# CPU.net
KiCad netlist of a schematic drawn in Altium Designer
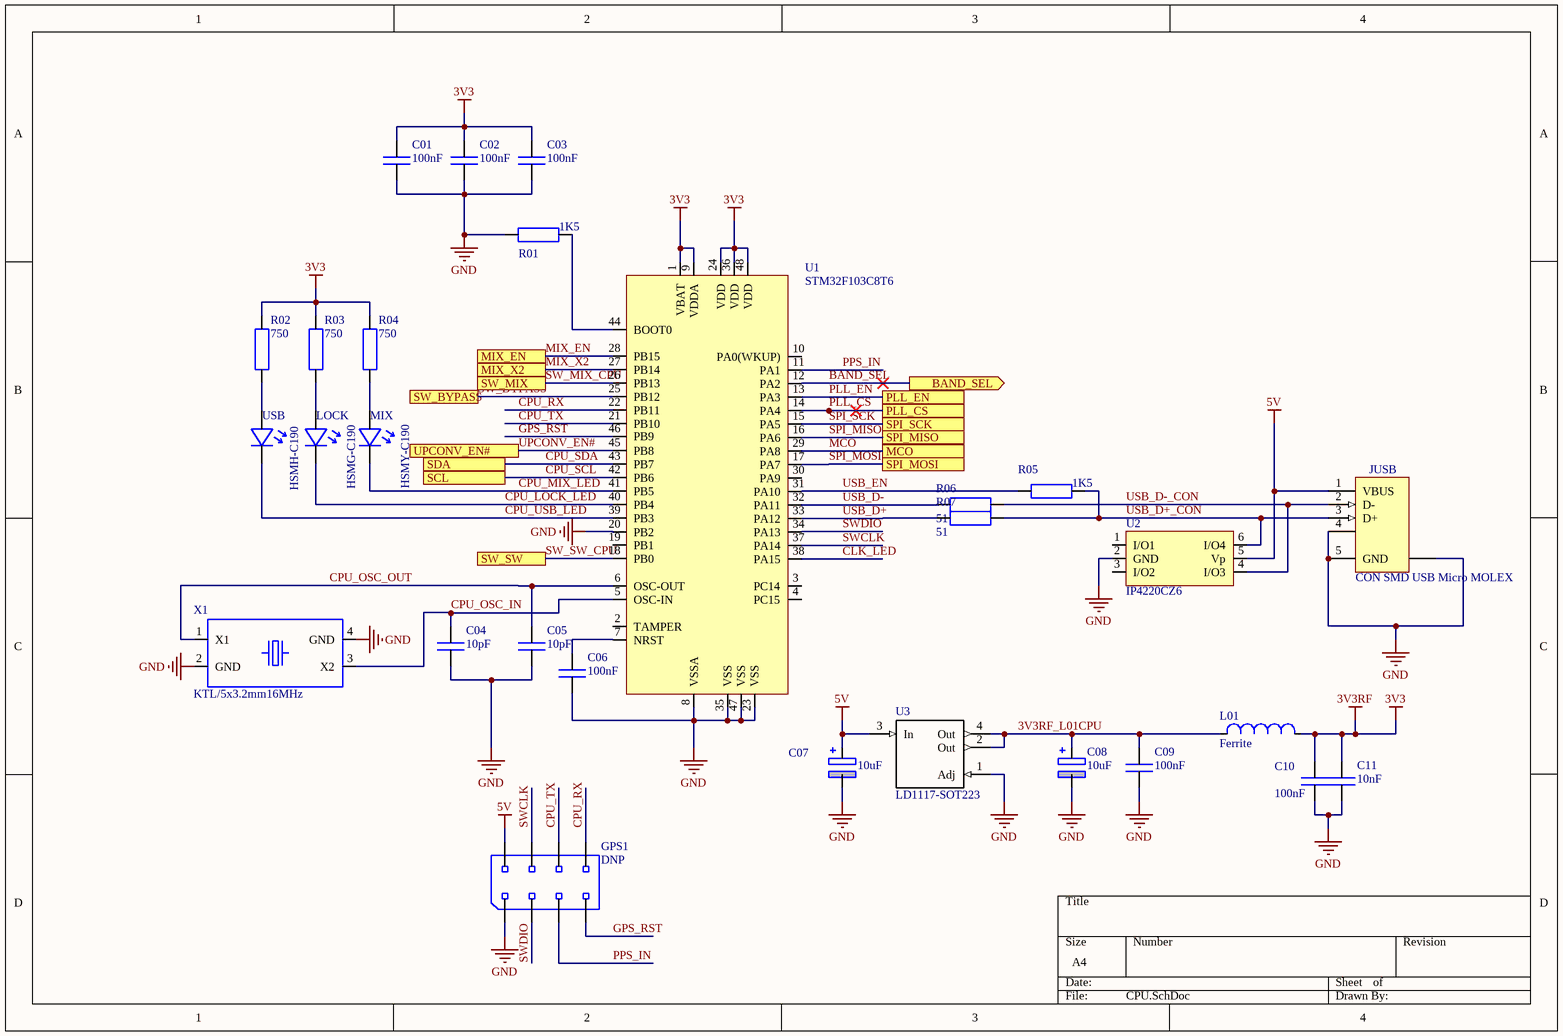
[diagram p0: CPU.SchDoc]

(export (version "E")
  (design (tool "Eeschema 10.0.6"))
  (components
    (comp (ref "C01")
      (value "100nF")
      (footprint "smd C0603_0.80")
      (description "smd capaciteit, verp.0603, 100nF")
      (fields (field (name "PART NUMBER") "CSMD603/100nF"))
      (libsource (lib "CDE_Library") (part "CSMD603/100nF"))
    )
    (comp (ref "C02")
      (value "100nF")
      (footprint "smd C0603_0.80")
      (description "smd capaciteit, verp.0603, 100nF")
      (fields (field (name "PART NUMBER") "CSMD603/100nF"))
      (libsource (lib "CDE_Library") (part "CSMD603/100nF"))
    )
    (comp (ref "C03")
      (value "100nF")
      (footprint "smd C0603_0.80")
      (description "smd capaciteit, verp.0603, 100nF")
      (fields (field (name "PART NUMBER") "CSMD603/100nF"))
      (libsource (lib "CDE_Library") (part "CSMD603/100nF"))
    )
    (comp (ref "C04")
      (value "10pF")
      (footprint "smd C0603_0.80")
      (description "smd capaciteit, verp.0603, 10pF")
      (fields (field (name "PART NUMBER") "CSMD603/10pF"))
      (libsource (lib "CDE_Library") (part "CSMD603/10pF"))
    )
    (comp (ref "C05")
      (value "10pF")
      (footprint "smd C0603_0.80")
      (description "smd capaciteit, verp.0603, 10pF")
      (fields (field (name "PART NUMBER") "CSMD603/10pF"))
      (libsource (lib "CDE_Library") (part "CSMD603/10pF"))
    )
    (comp (ref "C06")
      (value "100nF")
      (footprint "smd C0603_0.80")
      (description "smd capaciteit, verp.0603, 100nF")
      (fields (field (name "PART NUMBER") "CSMD603/100nF"))
      (libsource (lib "CDE_Library") (part "CSMD603/100nF"))
    )
    (comp (ref "C07")
      (value "10uF")
      (footprint "smd C1206 polar")
      (description "smd capaciteit, tantalium, verp.1206, 10uF/10V")
      (fields (field (name "PART NUMBER") "CSMD1206/10uF/10V"))
      (libsource (lib "CDE_Library") (part "CSMD1206/10uF/10V"))
    )
    (comp (ref "C08")
      (value "10uF")
      (footprint "smd C1206 polar")
      (description "smd capaciteit, tantalium, verp.1206, 10uF/10V")
      (fields (field (name "PART NUMBER") "CSMD1206/10uF/10V"))
      (libsource (lib "CDE_Library") (part "CSMD1206/10uF/10V"))
    )
    (comp (ref "C09")
      (value "100nF")
      (footprint "smd C0603_0.80")
      (description "smd capaciteit, verp.0603, 100nF")
      (fields (field (name "PART NUMBER") "CSMD603/100nF"))
      (libsource (lib "CDE_Library") (part "CSMD603/100nF"))
    )
    (comp (ref "C10")
      (value "100nF")
      (footprint "smd C0603_0.80")
      (description "smd capaciteit, verp.0603, 100nF")
      (fields (field (name "PART NUMBER") "CSMD603/100nF"))
      (libsource (lib "CDE_Library") (part "CSMD603/100nF"))
    )
    (comp (ref "C11")
      (value "10nF")
      (footprint "smd C0603_0.80")
      (description "smd capaciteit, verp.0603, 10nF")
      (fields (field (name "PART NUMBER") "CSMD603/10nF"))
      (libsource (lib "CDE_Library") (part "CSMD603/10nF"))
    )
    (comp (ref "GPS1")
      (value "DNP")
      (footprint "hdr 2x4")
      (description "pcb header recht 2x4  pitch 100mil")
      (fields (field (name "PART NUMBER") "CON HDR 2x4"))
      (libsource (lib "CDE_Library") (part "CON HDR 2x4"))
    )
    (comp (ref "JUSB")
      (value "CON SMD USB Micro MOLEX")
      (footprint "SMD USB MOLEX")
      (description "MOLEX - 47589-0001 - MICRO USB TYPE AB")
      (libsource (lib "CDE_Library") (part "CON SMD USB Micro MOLEX"))
    )
    (comp (ref "L01")
      (value "Ferrite")
      (footprint "smd C0805")
      (description "Ferrite bead, 0805 package")
      (libsource (lib "CDE_Library") (part "Ferrite 0805"))
    )
    (comp (ref "LOCK")
      (value "HSMG-C190")
      (footprint "led HSMH-C190 (Avago Technologies)")
      (description "led smd groen, Avago Techn., HSMG-C190")
      (libsource (lib "CDE_Library") (part "HSMG-C190"))
    )
    (comp (ref "MIX")
      (value "HSMY-C190")
      (footprint "led HSMH-C190 (Avago Technologies)")
      (description "led smd geel, Avago Techn., HSMY-C190")
      (libsource (lib "CDE_Library") (part "HSMY-C190"))
    )
    (comp (ref "R01")
      (value "1K5")
      (footprint "smd C0603_0.45")
      (description "weerstand SMD603, 1K5")
      (libsource (lib "CDE_Library") (part "1K5/603"))
    )
    (comp (ref "R02")
      (value "750")
      (footprint "smd C0603_0.45")
      (description "weerstand SMD603, 750R")
      (libsource (lib "CDE_Library") (part "750R/603"))
    )
    (comp (ref "R03")
      (value "750")
      (footprint "smd C0603_0.45")
      (description "weerstand SMD603, 750R")
      (libsource (lib "CDE_Library") (part "750R/603"))
    )
    (comp (ref "R04")
      (value "750")
      (footprint "smd C0603_0.45")
      (description "weerstand SMD603, 750R")
      (libsource (lib "CDE_Library") (part "750R/603"))
    )
    (comp (ref "R05")
      (value "1K5")
      (footprint "smd C0603_0.45")
      (description "weerstand SMD603, 1K5")
      (libsource (lib "CDE_Library") (part "1K5/603"))
    )
    (comp (ref "R06")
      (value "51")
      (footprint "smd C0603_0.45")
      (description "weerstand SMD603, 51R")
      (libsource (lib "CDE_Library") (part "51R/603"))
    )
    (comp (ref "R07")
      (value "51")
      (footprint "smd C0603_0.45")
      (description "weerstand SMD603, 51R")
      (libsource (lib "CDE_Library") (part "51R/603"))
    )
    (comp (ref "U1")
      (value "STM32F103C8T6")
      (footprint "TSQFP50P900X900X160-48N")
      (libsource (lib "library") (part "STM32F100xx"))
    )
    (comp (ref "U2")
      (value "IP4220CZ6")
      (footprint "smd SOT-457")
      (description "Dual USB 2.0 integrated ESD protection")
      (libsource (lib "CDE_Library") (part "IP4220CZ6"))
    )
    (comp (ref "U3")
      (value "LD1117-SOT223")
      (footprint "SOT223")
      (libsource (lib "vh_altium_library") (part "LD1117-SOT223"))
    )
    (comp (ref "USB")
      (value "HSMH-C190")
      (footprint "led HSMH-C190 (Avago Technologies)")
      (description "led smd rood, Avago Techn., HSMH-C190")
      (libsource (lib "CDE_Library") (part "HSMH-C190"))
    )
    (comp (ref "X1")
      (value "KTL/5x3.2mm16MHz")
      (footprint "smd KTL 5x3.2")
      (description "TXC Xtal 16.000 MHz, 5x3.2mm")
      (fields (field (name "PART NUMBER") "KTL/5x3.2mm 16MHz"))
      (libsource (lib "CDE_Library_local") (part "KTL/5x3.2mm 16MHz"))
    )
  )
  (nets
    (net (code "1") (name "/3V3RF_L01CPU") (class "Default")
      (node (ref "C08") (pin "1") (pintype "passive"))
      (node (ref "C09") (pin "2") (pintype "passive"))
      (node (ref "L01") (pin "1") (pintype "passive"))
      (node (ref "U3") (pin "2") (pinfunction "Out_2") (pintype "output"))
      (node (ref "U3") (pin "4") (pinfunction "Out_4") (pintype "output"))
    )
    (net (code "2") (name "/BAND_SEL") (class "Default")
      (node (ref "U1") (pin "12") (pinfunction "PA2_12") (pintype "passive"))
    )
    (net (code "3") (name "/CLK_LED") (class "Default")
      (node (ref "U1") (pin "38") (pinfunction "PA15_38") (pintype "passive"))
    )
    (net (code "4") (name "/CPU_LOCK_LED") (class "Default")
      (node (ref "LOCK") (pin "2") (pintype "passive"))
      (node (ref "U1") (pin "40") (pinfunction "PB4_40") (pintype "passive"))
    )
    (net (code "5") (name "/CPU_MIX_LED") (class "Default")
      (node (ref "MIX") (pin "2") (pintype "passive"))
      (node (ref "U1") (pin "41") (pinfunction "PB5_41") (pintype "passive"))
    )
    (net (code "6") (name "/CPU_OSC_IN") (class "Default")
      (node (ref "C04") (pin "2") (pintype "passive"))
      (node (ref "U1") (pin "5") (pinfunction "OSC-IN_5") (pintype "passive"))
      (node (ref "X1") (pin "3") (pinfunction "X2_3") (pintype "passive"))
    )
    (net (code "7") (name "/CPU_OSC_OUT") (class "Default")
      (node (ref "C05") (pin "2") (pintype "passive"))
      (node (ref "U1") (pin "6") (pinfunction "OSC-OUT_6") (pintype "passive"))
      (node (ref "X1") (pin "1") (pinfunction "X1_1") (pintype "passive"))
    )
    (net (code "8") (name "/CPU_RX") (class "Default")
      (node (ref "GPS1") (pin "8") (pintype "passive"))
      (node (ref "U1") (pin "22") (pinfunction "PB11_22") (pintype "passive"))
    )
    (net (code "9") (name "/CPU_SCL") (class "Default")
      (node (ref "U1") (pin "42") (pinfunction "PB6_42") (pintype "passive"))
    )
    (net (code "10") (name "/CPU_SDA") (class "Default")
      (node (ref "U1") (pin "43") (pinfunction "PB7_43") (pintype "passive"))
    )
    (net (code "11") (name "/CPU_TX") (class "Default")
      (node (ref "GPS1") (pin "6") (pintype "passive"))
      (node (ref "U1") (pin "21") (pinfunction "PB10_21") (pintype "passive"))
    )
    (net (code "12") (name "/CPU_USB_LED") (class "Default")
      (node (ref "U1") (pin "39") (pinfunction "PB3_39") (pintype "passive"))
      (node (ref "USB") (pin "2") (pintype "passive"))
    )
    (net (code "13") (name "/GPS_RST") (class "Default")
      (node (ref "GPS1") (pin "7") (pintype "passive"))
      (node (ref "U1") (pin "46") (pinfunction "PB9_46") (pintype "passive"))
    )
    (net (code "14") (name "/MCO") (class "Default")
      (node (ref "U1") (pin "29") (pinfunction "PA8_29") (pintype "passive"))
    )
    (net (code "15") (name "/MIX_EN") (class "Default")
      (node (ref "U1") (pin "28") (pinfunction "PB15_28") (pintype "passive"))
    )
    (net (code "16") (name "/MIX_X2") (class "Default")
      (node (ref "U1") (pin "27") (pinfunction "PB14_27") (pintype "passive"))
    )
    (net (code "17") (name "/PLL_CS") (class "Default")
      (node (ref "U1") (pin "14") (pinfunction "PA4_14") (pintype "passive"))
    )
    (net (code "18") (name "/PLL_EN") (class "Default")
      (node (ref "U1") (pin "13") (pinfunction "PA3_13") (pintype "passive"))
    )
    (net (code "19") (name "/PPS_IN") (class "Default")
      (node (ref "GPS1") (pin "5") (pintype "passive"))
      (node (ref "U1") (pin "11") (pinfunction "PA1_11") (pintype "passive"))
    )
    (net (code "20") (name "/SPI_MISO") (class "Default")
      (node (ref "U1") (pin "16") (pinfunction "PA6_16") (pintype "passive"))
    )
    (net (code "21") (name "/SPI_MOSI") (class "Default")
      (node (ref "U1") (pin "17") (pinfunction "PA7_17") (pintype "passive"))
    )
    (net (code "22") (name "/SPI_SCK") (class "Default")
      (node (ref "U1") (pin "15") (pinfunction "PA5_15") (pintype "passive"))
    )
    (net (code "23") (name "/SWCLK") (class "Default")
      (node (ref "GPS1") (pin "4") (pintype "passive"))
      (node (ref "U1") (pin "37") (pinfunction "PA14_37") (pintype "passive"))
    )
    (net (code "24") (name "/SWDIO") (class "Default")
      (node (ref "GPS1") (pin "3") (pintype "passive"))
      (node (ref "U1") (pin "34") (pinfunction "PA13_34") (pintype "passive"))
    )
    (net (code "25") (name "/SW_BYPASS") (class "Default")
      (node (ref "U1") (pin "25") (pinfunction "PB12_25") (pintype "passive"))
    )
    (net (code "26") (name "/SW_MIX_CPU") (class "Default")
      (node (ref "U1") (pin "26") (pinfunction "PB13_26") (pintype "passive"))
    )
    (net (code "27") (name "/SW_SW_CPU") (class "Default")
      (node (ref "U1") (pin "18") (pinfunction "PB0_18") (pintype "passive"))
    )
    (net (code "28") (name "/UPCONV_EN#") (class "Default")
      (node (ref "U1") (pin "45") (pinfunction "PB8_45") (pintype "passive"))
    )
    (net (code "29") (name "/USB_D+") (class "Default")
      (node (ref "R07") (pin "1") (pintype "passive"))
      (node (ref "U1") (pin "33") (pinfunction "PA12_33") (pintype "passive"))
    )
    (net (code "30") (name "/USB_D+_CON") (class "Default")
      (node (ref "JUSB") (pin "3") (pinfunction "D+_3") (pintype "input"))
      (node (ref "R05") (pin "2") (pintype "passive"))
      (node (ref "R07") (pin "2") (pintype "passive"))
      (node (ref "U2") (pin "6") (pinfunction "I/O4_6") (pintype "passive"))
    )
    (net (code "31") (name "/USB_D-") (class "Default")
      (node (ref "R06") (pin "1") (pintype "passive"))
      (node (ref "U1") (pin "32") (pinfunction "PA11_32") (pintype "passive"))
    )
    (net (code "32") (name "/USB_D-_CON") (class "Default")
      (node (ref "JUSB") (pin "2") (pinfunction "D-_2") (pintype "input"))
      (node (ref "R06") (pin "2") (pintype "passive"))
      (node (ref "U2") (pin "4") (pinfunction "I/O3_4") (pintype "passive"))
    )
    (net (code "33") (name "/USB_EN") (class "Default")
      (node (ref "R05") (pin "1") (pintype "passive"))
      (node (ref "U1") (pin "31") (pinfunction "PA10_31") (pintype "passive"))
    )
    (net (code "34") (name "3V3") (class "Default")
      (node (ref "C01") (pin "2") (pintype "passive"))
      (node (ref "C02") (pin "2") (pintype "passive"))
      (node (ref "C03") (pin "2") (pintype "passive"))
      (node (ref "C10") (pin "2") (pintype "passive"))
      (node (ref "C11") (pin "2") (pintype "passive"))
      (node (ref "L01") (pin "2") (pintype "passive"))
      (node (ref "R02") (pin "2") (pintype "passive"))
      (node (ref "R03") (pin "2") (pintype "passive"))
      (node (ref "R04") (pin "2") (pintype "passive"))
      (node (ref "U1") (pin "1") (pinfunction "VBAT_1") (pintype "passive"))
      (node (ref "U1") (pin "24") (pinfunction "VDD_24") (pintype "passive"))
      (node (ref "U1") (pin "36") (pinfunction "VDD_36") (pintype "passive"))
      (node (ref "U1") (pin "48") (pinfunction "VDD_48") (pintype "passive"))
      (node (ref "U1") (pin "9") (pinfunction "VDDA_9") (pintype "passive"))
    )
    (net (code "35") (name "5V") (class "Default")
      (node (ref "C07") (pin "1") (pintype "passive"))
      (node (ref "GPS1") (pin "2") (pintype "passive"))
      (node (ref "JUSB") (pin "1") (pinfunction "VBUS_1") (pintype "power_in"))
      (node (ref "U2") (pin "5") (pinfunction "Vp_5") (pintype "passive"))
      (node (ref "U3") (pin "3") (pinfunction "In_3") (pintype "input"))
    )
    (net (code "36") (name "GND") (class "Default")
      (node (ref "C01") (pin "1") (pintype "passive"))
      (node (ref "C02") (pin "1") (pintype "passive"))
      (node (ref "C03") (pin "1") (pintype "passive"))
      (node (ref "C04") (pin "1") (pintype "passive"))
      (node (ref "C05") (pin "1") (pintype "passive"))
      (node (ref "C06") (pin "1") (pintype "passive"))
      (node (ref "C07") (pin "2") (pintype "passive"))
      (node (ref "C08") (pin "2") (pintype "passive"))
      (node (ref "C09") (pin "1") (pintype "passive"))
      (node (ref "C10") (pin "1") (pintype "passive"))
      (node (ref "C11") (pin "1") (pintype "passive"))
      (node (ref "GPS1") (pin "1") (pintype "passive"))
      (node (ref "JUSB") (pin "4") (pinfunction "GND_4") (pintype "power_in"))
      (node (ref "JUSB") (pin "5") (pinfunction "GND_5") (pintype "passive"))
      (node (ref "JUSB") (pin "6") (pinfunction "SHLD_6") (pintype "passive"))
      (node (ref "R01") (pin "1") (pintype "passive"))
      (node (ref "U1") (pin "20") (pinfunction "PB2_20") (pintype "passive"))
      (node (ref "U1") (pin "23") (pinfunction "VSS_23") (pintype "passive"))
      (node (ref "U1") (pin "35") (pinfunction "VSS_35") (pintype "passive"))
      (node (ref "U1") (pin "47") (pinfunction "VSS_47") (pintype "passive"))
      (node (ref "U1") (pin "8") (pinfunction "VSSA_8") (pintype "passive"))
      (node (ref "U2") (pin "2") (pinfunction "GND_2") (pintype "passive"))
      (node (ref "U3") (pin "1") (pinfunction "Adj_1") (pintype "input"))
      (node (ref "X1") (pin "2") (pinfunction "GND_2") (pintype "passive"))
      (node (ref "X1") (pin "4") (pinfunction "GND_4") (pintype "passive"))
    )
    (net (code "37") (name "Net-(LOCK-Pad1)") (class "Default")
      (node (ref "LOCK") (pin "1") (pintype "passive"))
      (node (ref "R03") (pin "1") (pintype "passive"))
    )
    (net (code "38") (name "Net-(MIX-Pad1)") (class "Default")
      (node (ref "MIX") (pin "1") (pintype "passive"))
      (node (ref "R04") (pin "1") (pintype "passive"))
    )
    (net (code "39") (name "Net-(R02-Pad1)") (class "Default")
      (node (ref "R02") (pin "1") (pintype "passive"))
      (node (ref "USB") (pin "1") (pintype "passive"))
    )
    (net (code "40") (name "Net-(U1-BOOT0)") (class "Default")
      (node (ref "R01") (pin "2") (pintype "passive"))
      (node (ref "U1") (pin "44") (pinfunction "BOOT0_44") (pintype "passive"))
    )
    (net (code "41") (name "Net-(U1-NRST)") (class "Default")
      (node (ref "C06") (pin "2") (pintype "passive"))
      (node (ref "U1") (pin "7") (pinfunction "NRST_7") (pintype "passive"))
    )
    (net (code "42") (name "unconnected-(U1-PA0(WKUP)-Pad10)") (class "Default")
      (node (ref "U1") (pin "10") (pinfunction "PA0(WKUP)_10") (pintype "passive"))
    )
    (net (code "43") (name "unconnected-(U1-PA9-Pad30)") (class "Default")
      (node (ref "U1") (pin "30") (pinfunction "PA9_30") (pintype "passive"))
    )
    (net (code "44") (name "unconnected-(U1-PB1-Pad19)") (class "Default")
      (node (ref "U1") (pin "19") (pinfunction "PB1_19") (pintype "passive"))
    )
    (net (code "45") (name "unconnected-(U1-PC14-Pad3)") (class "Default")
      (node (ref "U1") (pin "3") (pinfunction "PC14_3") (pintype "passive"))
    )
    (net (code "46") (name "unconnected-(U1-PC15-Pad4)") (class "Default")
      (node (ref "U1") (pin "4") (pinfunction "PC15_4") (pintype "passive"))
    )
    (net (code "47") (name "unconnected-(U1-TAMPER-Pad2)") (class "Default")
      (node (ref "U1") (pin "2") (pinfunction "TAMPER_2") (pintype "passive"))
    )
    (net (code "48") (name "unconnected-(U2-I{slash}O1-Pad1)") (class "Default")
      (node (ref "U2") (pin "1") (pinfunction "I/O1_1") (pintype "passive"))
    )
    (net (code "49") (name "unconnected-(U2-I{slash}O2-Pad3)") (class "Default")
      (node (ref "U2") (pin "3") (pinfunction "I/O2_3") (pintype "passive"))
    )
  )
)
